# clock_rev0.net
KiCad netlist of a schematic drawn in EAGLE
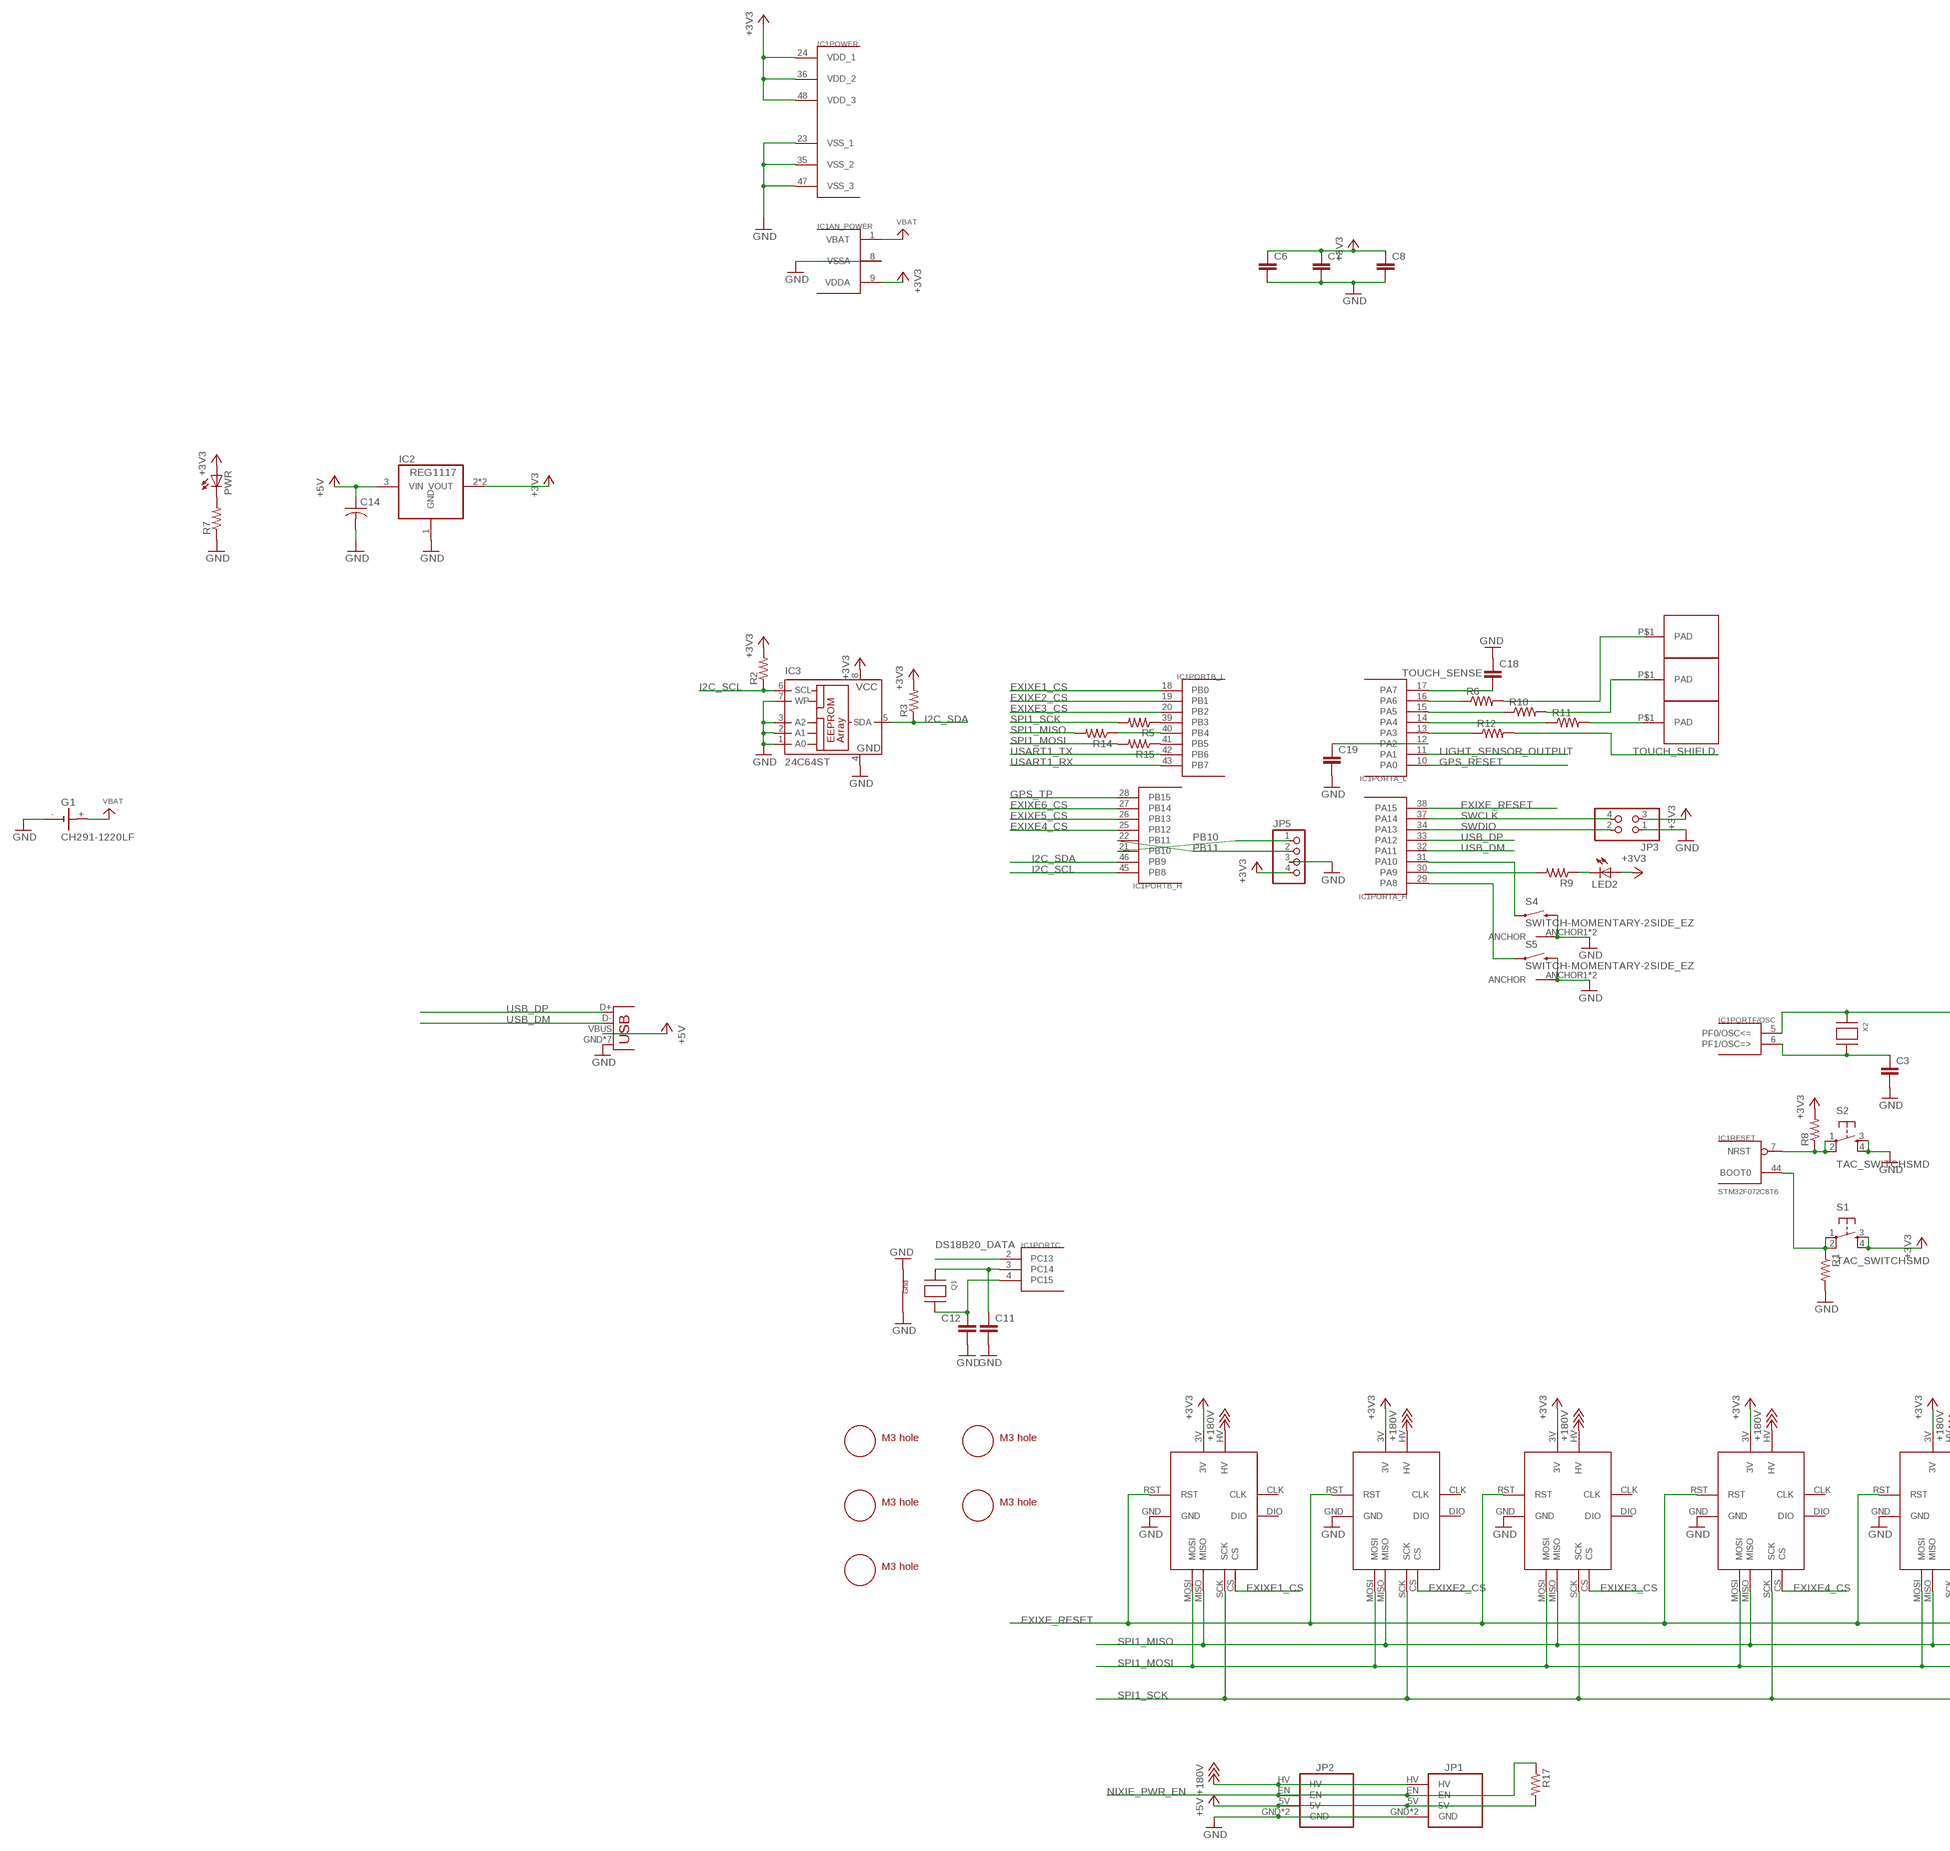
[diagram p0: schematic, sheet 1, part 1 of 2]
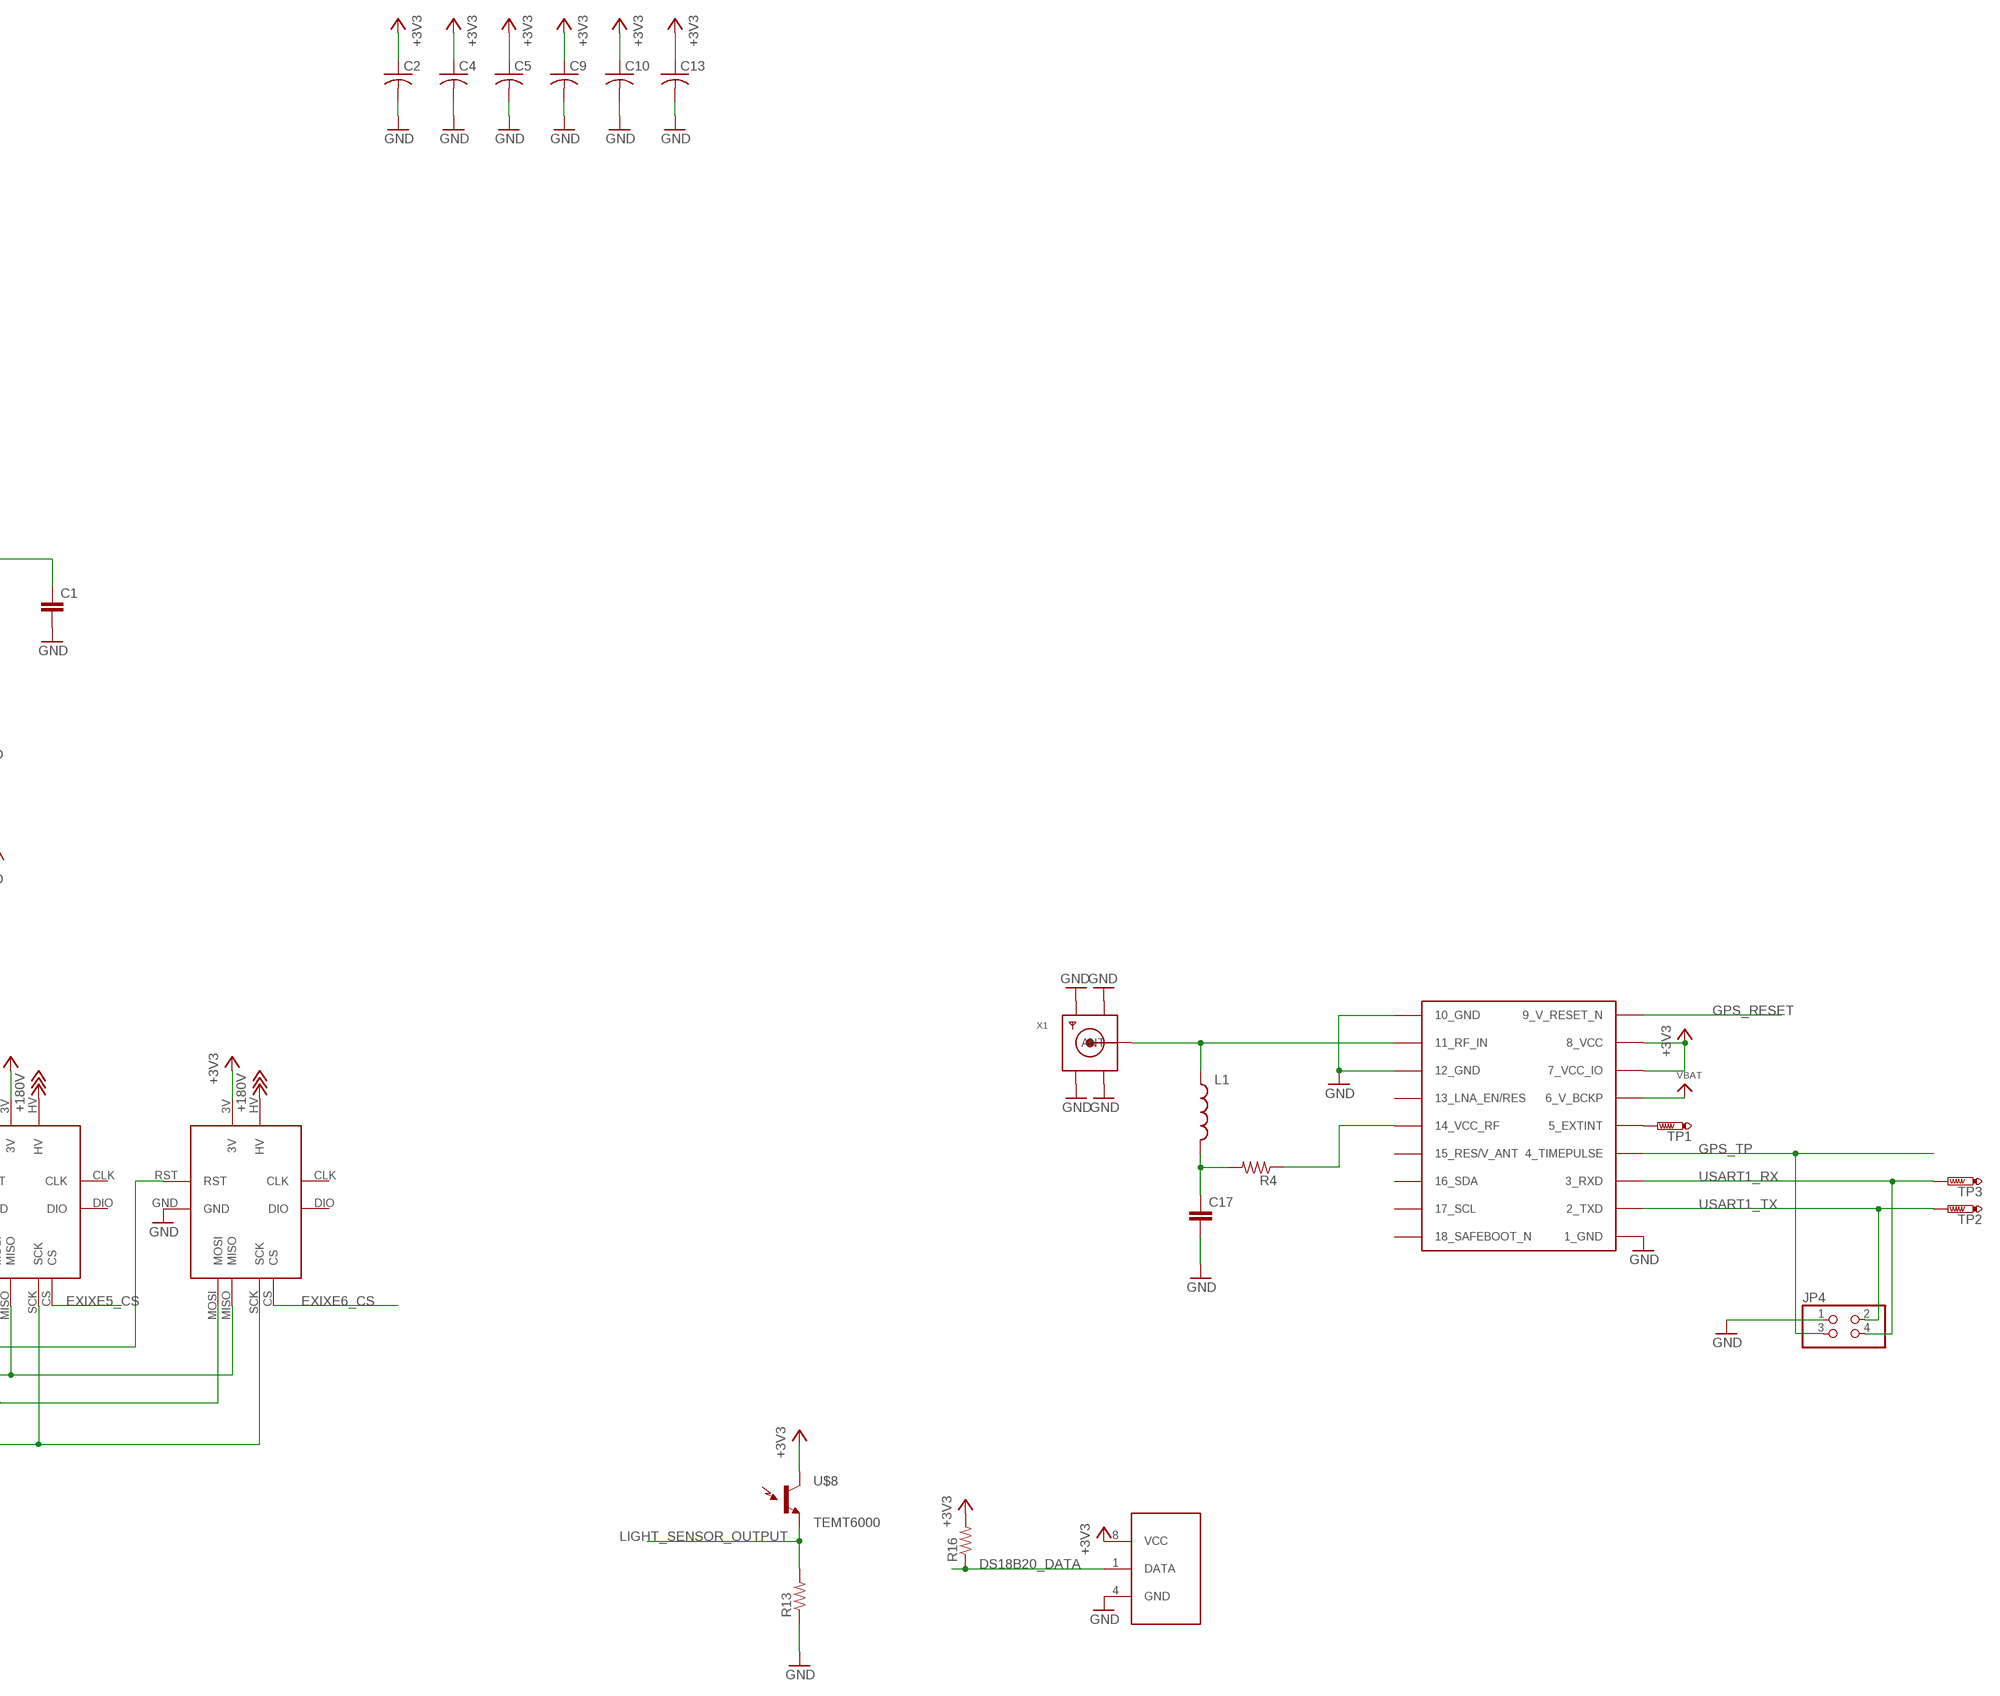
[diagram p1: schematic, sheet 1, part 2 of 2]

(export (version "E")
  (design (tool "Eeschema 10.0.6"))
  (components
    (comp (ref "C1")
      (value "CAP0805")
      (footprint "eagle-import:0805")
      (libsource (lib "eagle-import") (part "CAP0805"))
    )
    (comp (ref "C2")
      (value "C-USC1210")
      (footprint "eagle-import:C1210")
      (libsource (lib "eagle-import") (part "C-USC1210"))
    )
    (comp (ref "C3")
      (value "CAP0805")
      (footprint "eagle-import:0805")
      (libsource (lib "eagle-import") (part "CAP0805"))
    )
    (comp (ref "C4")
      (value "C-USC1210")
      (footprint "eagle-import:C1210")
      (libsource (lib "eagle-import") (part "C-USC1210"))
    )
    (comp (ref "C5")
      (value "C-USC1210")
      (footprint "eagle-import:C1210")
      (libsource (lib "eagle-import") (part "C-USC1210"))
    )
    (comp (ref "C6")
      (value "CAP0805")
      (footprint "eagle-import:0805")
      (libsource (lib "eagle-import") (part "CAP0805"))
    )
    (comp (ref "C7")
      (value "CAP0805")
      (footprint "eagle-import:0805")
      (libsource (lib "eagle-import") (part "CAP0805"))
    )
    (comp (ref "C8")
      (value "CAP0805")
      (footprint "eagle-import:0805")
      (libsource (lib "eagle-import") (part "CAP0805"))
    )
    (comp (ref "C9")
      (value "C-USC1210")
      (footprint "eagle-import:C1210")
      (libsource (lib "eagle-import") (part "C-USC1210"))
    )
    (comp (ref "C10")
      (value "C-USC1210")
      (footprint "eagle-import:C1210")
      (libsource (lib "eagle-import") (part "C-USC1210"))
    )
    (comp (ref "C11")
      (value "CAP0805")
      (footprint "eagle-import:0805")
      (libsource (lib "eagle-import") (part "CAP0805"))
    )
    (comp (ref "C12")
      (value "CAP0805")
      (footprint "eagle-import:0805")
      (libsource (lib "eagle-import") (part "CAP0805"))
    )
    (comp (ref "C13")
      (value "C-USC1210")
      (footprint "eagle-import:C1210")
      (libsource (lib "eagle-import") (part "C-USC1210"))
    )
    (comp (ref "C14")
      (value "C-USC1210")
      (footprint "eagle-import:C1210")
      (libsource (lib "eagle-import") (part "C-USC1210"))
    )
    (comp (ref "C17")
      (value "CAP0805")
      (footprint "eagle-import:0805")
      (libsource (lib "eagle-import") (part "CAP0805"))
    )
    (comp (ref "C18")
      (value "CAP0805")
      (footprint "eagle-import:0805")
      (libsource (lib "eagle-import") (part "CAP0805"))
    )
    (comp (ref "C19")
      (value "CAP0805")
      (footprint "eagle-import:0805")
      (libsource (lib "eagle-import") (part "CAP0805"))
    )
    (comp (ref "G1")
      (value "CH291-1220LF")
      (footprint "eagle-import:CH291-1220LF")
      (libsource (lib "eagle-import") (part "CH291-1220LF"))
    )
    (comp (ref "IC1")
      (value "STM32F072C8T6")
      (footprint "eagle-import:TQFP48")
      (libsource (lib "eagle-import") (part "STM32F072C8T6"))
    )
    (comp (ref "IC2")
      (value "REG1117")
      (footprint "eagle-import:SOT223")
      (libsource (lib "eagle-import") (part "REG1117"))
    )
    (comp (ref "IC3")
      (value "24C64ST")
      (footprint "eagle-import:TSSOP8")
      (fields (field (name "MPN") "CAT24C64YI-GT3"))
      (libsource (lib "eagle-import") (part "24STC64"))
    )
    (comp (ref "JP1")
      (value "EBAY_MODULEEBAY")
      (footprint "eagle-import:EBAY_PKG")
      (libsource (lib "eagle-import") (part "EBAY_MODULEEBAY"))
    )
    (comp (ref "JP2")
      (value "EBAY_MODULETAOBAO")
      (footprint "eagle-import:TAOBAO_PKG")
      (libsource (lib "eagle-import") (part "EBAY_MODULETAOBAO"))
    )
    (comp (ref "JP3")
      (value "PINHD-2X2")
      (footprint "eagle-import:2X02")
      (libsource (lib "eagle-import") (part "PINHD-2X2"))
    )
    (comp (ref "JP4")
      (value "PINHD-2X2")
      (footprint "eagle-import:2X02")
      (libsource (lib "eagle-import") (part "PINHD-2X2"))
    )
    (comp (ref "JP5")
      (value "PINHD-1X4")
      (footprint "eagle-import:1X04")
      (libsource (lib "eagle-import") (part "PINHD-1X4"))
    )
    (comp (ref "L1")
      (value "INDUCTOR0805")
      (footprint "eagle-import:0805")
      (libsource (lib "eagle-import") (part "INDUCTOR0805"))
    )
    (comp (ref "LED2")
      (value "LEDCHIP-LED0805")
      (footprint "eagle-import:CHIP-LED0805")
      (libsource (lib "eagle-import") (part "LEDCHIP-LED0805"))
    )
    (comp (ref "PWR")
      (value "LEDCHIP-LED0805")
      (footprint "eagle-import:CHIP-LED0805")
      (libsource (lib "eagle-import") (part "LEDCHIP-LED0805"))
    )
    (comp (ref "Q1")
      (value "XTAL-4-3225")
      (footprint "eagle-import:NX3225")
      (libsource (lib "eagle-import") (part "XTAL-4-3225"))
    )
    (comp (ref "R1")
      (value "RESISTOR0805-RES")
      (footprint "eagle-import:0805")
      (libsource (lib "eagle-import") (part "RESISTOR0805-RES"))
    )
    (comp (ref "R2")
      (value "RESISTOR0805-RES")
      (footprint "eagle-import:0805")
      (libsource (lib "eagle-import") (part "RESISTOR0805-RES"))
    )
    (comp (ref "R3")
      (value "RESISTOR0805-RES")
      (footprint "eagle-import:0805")
      (libsource (lib "eagle-import") (part "RESISTOR0805-RES"))
    )
    (comp (ref "R4")
      (value "RESISTOR0805-RES")
      (footprint "eagle-import:0805")
      (libsource (lib "eagle-import") (part "RESISTOR0805-RES"))
    )
    (comp (ref "R5")
      (value "RESISTOR0805-RES")
      (footprint "eagle-import:0805")
      (libsource (lib "eagle-import") (part "RESISTOR0805-RES"))
    )
    (comp (ref "R6")
      (value "RESISTOR0805-RES")
      (footprint "eagle-import:0805")
      (libsource (lib "eagle-import") (part "RESISTOR0805-RES"))
    )
    (comp (ref "R7")
      (value "RESISTOR0805-RES")
      (footprint "eagle-import:0805")
      (libsource (lib "eagle-import") (part "RESISTOR0805-RES"))
    )
    (comp (ref "R8")
      (value "RESISTOR0805-RES")
      (footprint "eagle-import:0805")
      (libsource (lib "eagle-import") (part "RESISTOR0805-RES"))
    )
    (comp (ref "R9")
      (value "RESISTOR0805-RES")
      (footprint "eagle-import:0805")
      (libsource (lib "eagle-import") (part "RESISTOR0805-RES"))
    )
    (comp (ref "R10")
      (value "RESISTOR0805-RES")
      (footprint "eagle-import:0805")
      (libsource (lib "eagle-import") (part "RESISTOR0805-RES"))
    )
    (comp (ref "R11")
      (value "RESISTOR0805-RES")
      (footprint "eagle-import:0805")
      (libsource (lib "eagle-import") (part "RESISTOR0805-RES"))
    )
    (comp (ref "R12")
      (value "RESISTOR0805-RES")
      (footprint "eagle-import:0805")
      (libsource (lib "eagle-import") (part "RESISTOR0805-RES"))
    )
    (comp (ref "R13")
      (value "RESISTOR0805-RES")
      (footprint "eagle-import:0805")
      (libsource (lib "eagle-import") (part "RESISTOR0805-RES"))
    )
    (comp (ref "R14")
      (value "RESISTOR0805-RES")
      (footprint "eagle-import:0805")
      (libsource (lib "eagle-import") (part "RESISTOR0805-RES"))
    )
    (comp (ref "R15")
      (value "RESISTOR0805-RES")
      (footprint "eagle-import:0805")
      (libsource (lib "eagle-import") (part "RESISTOR0805-RES"))
    )
    (comp (ref "R16")
      (value "RESISTOR0805-RES")
      (footprint "eagle-import:0805")
      (libsource (lib "eagle-import") (part "RESISTOR0805-RES"))
    )
    (comp (ref "R17")
      (value "RESISTOR0805-RES")
      (footprint "eagle-import:0805")
      (libsource (lib "eagle-import") (part "RESISTOR0805-RES"))
    )
    (comp (ref "S1")
      (value "TAC_SWITCHSMD")
      (footprint "eagle-import:TACTILE-SWITCH-SMD")
      (libsource (lib "eagle-import") (part "TAC_SWITCHSMD"))
    )
    (comp (ref "S2")
      (value "TAC_SWITCHSMD")
      (footprint "eagle-import:TACTILE-SWITCH-SMD")
      (libsource (lib "eagle-import") (part "TAC_SWITCHSMD"))
    )
    (comp (ref "S4")
      (value "SWITCH-MOMENTARY-2SIDE_EZ")
      (footprint "eagle-import:TACTILE-PTH-SIDEEZ")
      (libsource (lib "eagle-import") (part "SWITCH-MOMENTARY-2SIDE_EZ"))
    )
    (comp (ref "S5")
      (value "SWITCH-MOMENTARY-2SIDE_EZ")
      (footprint "eagle-import:TACTILE-PTH-SIDEEZ")
      (libsource (lib "eagle-import") (part "SWITCH-MOMENTARY-2SIDE_EZ"))
    )
    (comp (ref "TP1")
      (value "PTR1TP20R")
      (footprint "eagle-import:TP20R")
      (libsource (lib "eagle-import") (part "PTR1TP20R"))
    )
    (comp (ref "TP2")
      (value "PTR1TP20R")
      (footprint "eagle-import:TP20R")
      (libsource (lib "eagle-import") (part "PTR1TP20R"))
    )
    (comp (ref "TP3")
      (value "PTR1TP20R")
      (footprint "eagle-import:TP20R")
      (libsource (lib "eagle-import") (part "PTR1TP20R"))
    )
    (comp (ref "U$1")
      (value "EXIXE")
      (footprint "eagle-import:EXIXE_PAC")
      (libsource (lib "eagle-import") (part "EXIXE"))
    )
    (comp (ref "U$2")
      (value "EXIXE")
      (footprint "eagle-import:EXIXE_PAC")
      (libsource (lib "eagle-import") (part "EXIXE"))
    )
    (comp (ref "U$3")
      (value "EXIXE")
      (footprint "eagle-import:EXIXE_PAC")
      (libsource (lib "eagle-import") (part "EXIXE"))
    )
    (comp (ref "U$4")
      (value "EXIXE")
      (footprint "eagle-import:EXIXE_PAC")
      (libsource (lib "eagle-import") (part "EXIXE"))
    )
    (comp (ref "U$5")
      (value "EXIXE")
      (footprint "eagle-import:EXIXE_PAC")
      (libsource (lib "eagle-import") (part "EXIXE"))
    )
    (comp (ref "U$6")
      (value "EXIXE")
      (footprint "eagle-import:EXIXE_PAC")
      (libsource (lib "eagle-import") (part "EXIXE"))
    )
    (comp (ref "U$7")
      (value "MAX-M8")
      (footprint "eagle-import:MAX-M8")
      (libsource (lib "eagle-import") (part "MAX-M8"))
    )
    (comp (ref "U$8")
      (value "TEMT6000")
      (footprint "eagle-import:TEMT6000-SEN")
      (libsource (lib "eagle-import") (part "TEMT6000"))
    )
    (comp (ref "U$9")
      (value "DS18B20")
      (footprint "eagle-import:MSOP8")
      (libsource (lib "eagle-import") (part "DS18B20"))
    )
    (comp (ref "U$10")
      (value "M3_MOUNTING_HOLE")
      (footprint "eagle-import:M3_MOUNTING_HOLE_PACK")
      (libsource (lib "eagle-import") (part "M3_MOUNTING_HOLE"))
    )
    (comp (ref "U$11")
      (value "M3_MOUNTING_HOLE")
      (footprint "eagle-import:M3_MOUNTING_HOLE_PACK")
      (libsource (lib "eagle-import") (part "M3_MOUNTING_HOLE"))
    )
    (comp (ref "U$12")
      (value "M3_MOUNTING_HOLE")
      (footprint "eagle-import:M3_MOUNTING_HOLE_PACK")
      (libsource (lib "eagle-import") (part "M3_MOUNTING_HOLE"))
    )
    (comp (ref "U$13")
      (value "M3_MOUNTING_HOLE")
      (footprint "eagle-import:M3_MOUNTING_HOLE_PACK")
      (libsource (lib "eagle-import") (part "M3_MOUNTING_HOLE"))
    )
    (comp (ref "U$14")
      (value "TOUCHPAD")
      (footprint "eagle-import:TOUCHPAD_PAK")
      (libsource (lib "eagle-import") (part "TOUCHPAD"))
    )
    (comp (ref "U$15")
      (value "TOUCHPAD")
      (footprint "eagle-import:TOUCHPAD_PAK")
      (libsource (lib "eagle-import") (part "TOUCHPAD"))
    )
    (comp (ref "U$16")
      (value "TOUCHPAD")
      (footprint "eagle-import:TOUCHPAD_PAK")
      (libsource (lib "eagle-import") (part "TOUCHPAD"))
    )
    (comp (ref "U$20")
      (value "M3_MOUNTING_HOLE")
      (footprint "eagle-import:M3_MOUNTING_HOLE_PACK")
      (libsource (lib "eagle-import") (part "M3_MOUNTING_HOLE"))
    )
    (comp (ref "X1")
      (value "SMACONNECTOR")
      (footprint "eagle-import:SMA90_DIP")
      (libsource (lib "eagle-import") (part "SMACONNECTOR"))
    )
    (comp (ref "X2")
      (value "XTAL-3.2X1.5")
      (footprint "eagle-import:XTAL3215")
      (libsource (lib "eagle-import") (part "XTAL-3.2X1.5"))
    )
    (comp (ref "X3")
      (value "USB-MICROB")
      (footprint "eagle-import:USB-MICROB")
      (libsource (lib "eagle-import") (part "USB-MICROB"))
    )
  )
  (nets
    (net (code "1") (name "+3V3") (class "Default")
      (node (ref "C10") (pin "1") (pinfunction "1_1") (pintype "passive"))
      (node (ref "C13") (pin "1") (pinfunction "1_1") (pintype "passive"))
      (node (ref "C2") (pin "1") (pinfunction "1_1") (pintype "passive"))
      (node (ref "C4") (pin "1") (pinfunction "1_1") (pintype "passive"))
      (node (ref "C5") (pin "1") (pinfunction "1_1") (pintype "passive"))
      (node (ref "C6") (pin "1") (pinfunction "1_1") (pintype "passive"))
      (node (ref "C7") (pin "1") (pinfunction "1_1") (pintype "passive"))
      (node (ref "C8") (pin "1") (pinfunction "1_1") (pintype "passive"))
      (node (ref "C9") (pin "1") (pinfunction "1_1") (pintype "passive"))
      (node (ref "IC1") (pin "24") (pinfunction "VDD_1_24") (pintype "power_in"))
      (node (ref "IC1") (pin "36") (pinfunction "VDD_2_36") (pintype "power_in"))
      (node (ref "IC1") (pin "48") (pinfunction "VDD_3_48") (pintype "power_in"))
      (node (ref "IC1") (pin "9") (pinfunction "VDDA_9") (pintype "power_in"))
      (node (ref "IC2") (pin "2") (pinfunction "VOUT_2") (pintype "output"))
      (node (ref "IC2") (pin "4") (pinfunction "VOUT_4") (pintype "output"))
      (node (ref "IC3") (pin "8") (pinfunction "VCC_8") (pintype "power_in"))
      (node (ref "JP3") (pin "3") (pinfunction "3_3") (pintype "passive"))
      (node (ref "JP5") (pin "4") (pinfunction "4_4") (pintype "passive"))
      (node (ref "LED2") (pin "A") (pinfunction "A_A") (pintype "passive"))
      (node (ref "PWR") (pin "A") (pinfunction "A_A") (pintype "passive"))
      (node (ref "R16") (pin "2") (pinfunction "2_2") (pintype "passive"))
      (node (ref "R2") (pin "2") (pinfunction "2_2") (pintype "passive"))
      (node (ref "R3") (pin "2") (pinfunction "2_2") (pintype "passive"))
      (node (ref "R8") (pin "2") (pinfunction "2_2") (pintype "passive"))
      (node (ref "S1") (pin "3") (pinfunction "3_3") (pintype "passive"))
      (node (ref "S1") (pin "4") (pinfunction "4_4") (pintype "passive"))
      (node (ref "U$1") (pin "3V") (pinfunction "3V_3V") (pintype "bidirectional"))
      (node (ref "U$2") (pin "3V") (pinfunction "3V_3V") (pintype "bidirectional"))
      (node (ref "U$3") (pin "3V") (pinfunction "3V_3V") (pintype "bidirectional"))
      (node (ref "U$4") (pin "3V") (pinfunction "3V_3V") (pintype "bidirectional"))
      (node (ref "U$5") (pin "3V") (pinfunction "3V_3V") (pintype "bidirectional"))
      (node (ref "U$6") (pin "3V") (pinfunction "3V_3V") (pintype "bidirectional"))
      (node (ref "U$7") (pin "7_VCC_IO") (pinfunction "7_VCC_IO_7_VCC_IO") (pintype "power_in"))
      (node (ref "U$7") (pin "8_VCC") (pinfunction "8_VCC_8_VCC") (pintype "power_in"))
      (node (ref "U$8") (pin "COLLECTOR") (pinfunction "C1_COLLECTOR") (pintype "passive"))
      (node (ref "U$9") (pin "8") (pinfunction "VCC_8") (pintype "bidirectional"))
    )
    (net (code "2") (name "+5V") (class "Default")
      (node (ref "C14") (pin "1") (pinfunction "1_1") (pintype "passive"))
      (node (ref "IC2") (pin "3") (pinfunction "VIN_3") (pintype "input"))
      (node (ref "JP1") (pin "5V") (pinfunction "5V_5V") (pintype "bidirectional"))
      (node (ref "JP2") (pin "5V") (pinfunction "5V_5V") (pintype "bidirectional"))
      (node (ref "R17") (pin "2") (pinfunction "2_2") (pintype "passive"))
      (node (ref "X3") (pin "VBUS") (pinfunction "VBUS_VBUS") (pintype "bidirectional"))
    )
    (net (code "3") (name "+180V") (class "Default")
      (node (ref "JP1") (pin "HV") (pinfunction "HV_HV") (pintype "bidirectional"))
      (node (ref "JP2") (pin "HV") (pinfunction "HV_HV") (pintype "bidirectional"))
      (node (ref "U$1") (pin "HV") (pinfunction "HV_HV") (pintype "bidirectional"))
      (node (ref "U$2") (pin "HV") (pinfunction "HV_HV") (pintype "bidirectional"))
      (node (ref "U$3") (pin "HV") (pinfunction "HV_HV") (pintype "bidirectional"))
      (node (ref "U$4") (pin "HV") (pinfunction "HV_HV") (pintype "bidirectional"))
      (node (ref "U$5") (pin "HV") (pinfunction "HV_HV") (pintype "bidirectional"))
      (node (ref "U$6") (pin "HV") (pinfunction "HV_HV") (pintype "bidirectional"))
    )
    (net (code "4") (name "/DS18B20_DATA") (class "Default")
      (node (ref "IC1") (pin "2") (pinfunction "PC13_2") (pintype "bidirectional"))
      (node (ref "R16") (pin "1") (pinfunction "1_1") (pintype "passive"))
      (node (ref "U$9") (pin "1") (pinfunction "DATA_1") (pintype "bidirectional"))
    )
    (net (code "5") (name "/EXIXE1_CS") (class "Default")
      (node (ref "IC1") (pin "18") (pinfunction "PB0_18") (pintype "bidirectional"))
      (node (ref "U$1") (pin "CS") (pinfunction "CS_CS") (pintype "bidirectional"))
    )
    (net (code "6") (name "/EXIXE2_CS") (class "Default")
      (node (ref "IC1") (pin "19") (pinfunction "PB1_19") (pintype "bidirectional"))
      (node (ref "U$2") (pin "CS") (pinfunction "CS_CS") (pintype "bidirectional"))
    )
    (net (code "7") (name "/EXIXE3_CS") (class "Default")
      (node (ref "IC1") (pin "20") (pinfunction "PB2_20") (pintype "bidirectional"))
      (node (ref "U$3") (pin "CS") (pinfunction "CS_CS") (pintype "bidirectional"))
    )
    (net (code "8") (name "/EXIXE4_CS") (class "Default")
      (node (ref "IC1") (pin "25") (pinfunction "PB12_25") (pintype "bidirectional"))
      (node (ref "U$4") (pin "CS") (pinfunction "CS_CS") (pintype "bidirectional"))
    )
    (net (code "9") (name "/EXIXE5_CS") (class "Default")
      (node (ref "IC1") (pin "26") (pinfunction "PB13_26") (pintype "bidirectional"))
      (node (ref "U$5") (pin "CS") (pinfunction "CS_CS") (pintype "bidirectional"))
    )
    (net (code "10") (name "/EXIXE6_CS") (class "Default")
      (node (ref "IC1") (pin "27") (pinfunction "PB14_27") (pintype "bidirectional"))
      (node (ref "U$6") (pin "CS") (pinfunction "CS_CS") (pintype "bidirectional"))
    )
    (net (code "11") (name "/EXIXE_RESET") (class "Default")
      (node (ref "IC1") (pin "38") (pinfunction "PA15_38") (pintype "bidirectional"))
      (node (ref "U$1") (pin "RST") (pinfunction "RST_RST") (pintype "bidirectional"))
      (node (ref "U$2") (pin "RST") (pinfunction "RST_RST") (pintype "bidirectional"))
      (node (ref "U$3") (pin "RST") (pinfunction "RST_RST") (pintype "bidirectional"))
      (node (ref "U$4") (pin "RST") (pinfunction "RST_RST") (pintype "bidirectional"))
      (node (ref "U$5") (pin "RST") (pinfunction "RST_RST") (pintype "bidirectional"))
      (node (ref "U$6") (pin "RST") (pinfunction "RST_RST") (pintype "bidirectional"))
    )
    (net (code "12") (name "/GPS_RESET") (class "Default")
      (node (ref "IC1") (pin "10") (pinfunction "PA0_10") (pintype "bidirectional"))
      (node (ref "U$7") (pin "9_RESET_N") (pinfunction "9_V_RESET_N_9_RESET_N") (pintype "power_in"))
    )
    (net (code "13") (name "/GPS_TP") (class "Default")
      (node (ref "IC1") (pin "28") (pinfunction "PB15_28") (pintype "bidirectional"))
      (node (ref "JP4") (pin "3") (pinfunction "3_3") (pintype "passive"))
      (node (ref "U$7") (pin "4_TIMEPULSE") (pinfunction "4_TIMEPULSE_4_TIMEPULSE") (pintype "bidirectional"))
    )
    (net (code "14") (name "/I2C_SCL") (class "Default")
      (node (ref "IC1") (pin "45") (pinfunction "PB8_45") (pintype "bidirectional"))
      (node (ref "IC3") (pin "6") (pinfunction "SCL_6") (pintype "input"))
      (node (ref "R2") (pin "1") (pinfunction "1_1") (pintype "passive"))
    )
    (net (code "15") (name "/I2C_SDA") (class "Default")
      (node (ref "IC1") (pin "46") (pinfunction "PB9_46") (pintype "bidirectional"))
      (node (ref "IC3") (pin "5") (pinfunction "SDA_5") (pintype "bidirectional"))
      (node (ref "R3") (pin "1") (pinfunction "1_1") (pintype "passive"))
    )
    (net (code "16") (name "/LIGHT_SENSOR_OUTPUT") (class "Default")
      (node (ref "IC1") (pin "11") (pinfunction "PA1_11") (pintype "bidirectional"))
      (node (ref "R13") (pin "2") (pinfunction "2_2") (pintype "passive"))
      (node (ref "U$8") (pin "EMITTER") (pinfunction "E1_EMITTER") (pintype "passive"))
    )
    (net (code "17") (name "/NIXIE_PWR_EN") (class "Default")
      (node (ref "JP1") (pin "EN") (pinfunction "EN_EN") (pintype "bidirectional"))
      (node (ref "JP2") (pin "EN") (pinfunction "EN_EN") (pintype "bidirectional"))
      (node (ref "R17") (pin "1") (pinfunction "1_1") (pintype "passive"))
    )
    (net (code "18") (name "/PB10") (class "Default")
      (node (ref "IC1") (pin "21") (pinfunction "PB10_21") (pintype "bidirectional"))
      (node (ref "JP5") (pin "1") (pinfunction "1_1") (pintype "passive"))
    )
    (net (code "19") (name "/PB11") (class "Default")
      (node (ref "IC1") (pin "22") (pinfunction "PB11_22") (pintype "bidirectional"))
      (node (ref "JP5") (pin "2") (pinfunction "2_2") (pintype "passive"))
    )
    (net (code "20") (name "/SPI1_MISO") (class "Default")
      (node (ref "R14") (pin "2") (pinfunction "2_2") (pintype "passive"))
      (node (ref "U$1") (pin "MISO") (pinfunction "MISO_MISO") (pintype "bidirectional"))
      (node (ref "U$2") (pin "MISO") (pinfunction "MISO_MISO") (pintype "bidirectional"))
      (node (ref "U$3") (pin "MISO") (pinfunction "MISO_MISO") (pintype "bidirectional"))
      (node (ref "U$4") (pin "MISO") (pinfunction "MISO_MISO") (pintype "bidirectional"))
      (node (ref "U$5") (pin "MISO") (pinfunction "MISO_MISO") (pintype "bidirectional"))
      (node (ref "U$6") (pin "MISO") (pinfunction "MISO_MISO") (pintype "bidirectional"))
    )
    (net (code "21") (name "/SPI1_MOSI") (class "Default")
      (node (ref "R15") (pin "2") (pinfunction "2_2") (pintype "passive"))
      (node (ref "U$1") (pin "MOSI") (pinfunction "MOSI_MOSI") (pintype "bidirectional"))
      (node (ref "U$2") (pin "MOSI") (pinfunction "MOSI_MOSI") (pintype "bidirectional"))
      (node (ref "U$3") (pin "MOSI") (pinfunction "MOSI_MOSI") (pintype "bidirectional"))
      (node (ref "U$4") (pin "MOSI") (pinfunction "MOSI_MOSI") (pintype "bidirectional"))
      (node (ref "U$5") (pin "MOSI") (pinfunction "MOSI_MOSI") (pintype "bidirectional"))
      (node (ref "U$6") (pin "MOSI") (pinfunction "MOSI_MOSI") (pintype "bidirectional"))
    )
    (net (code "22") (name "/SPI1_SCK") (class "Default")
      (node (ref "R5") (pin "2") (pinfunction "2_2") (pintype "passive"))
      (node (ref "U$1") (pin "SCK") (pinfunction "SCK_SCK") (pintype "bidirectional"))
      (node (ref "U$2") (pin "SCK") (pinfunction "SCK_SCK") (pintype "bidirectional"))
      (node (ref "U$3") (pin "SCK") (pinfunction "SCK_SCK") (pintype "bidirectional"))
      (node (ref "U$4") (pin "SCK") (pinfunction "SCK_SCK") (pintype "bidirectional"))
      (node (ref "U$5") (pin "SCK") (pinfunction "SCK_SCK") (pintype "bidirectional"))
      (node (ref "U$6") (pin "SCK") (pinfunction "SCK_SCK") (pintype "bidirectional"))
    )
    (net (code "23") (name "/SWCLK") (class "Default")
      (node (ref "IC1") (pin "37") (pinfunction "PA14_37") (pintype "bidirectional"))
      (node (ref "JP3") (pin "4") (pinfunction "4_4") (pintype "passive"))
    )
    (net (code "24") (name "/SWDIO") (class "Default")
      (node (ref "IC1") (pin "34") (pinfunction "PA13_34") (pintype "bidirectional"))
      (node (ref "JP3") (pin "2") (pinfunction "2_2") (pintype "passive"))
    )
    (net (code "25") (name "/TOUCH_SENSE") (class "Default")
      (node (ref "C18") (pin "2") (pinfunction "2_2") (pintype "passive"))
      (node (ref "IC1") (pin "17") (pinfunction "PA7_17") (pintype "bidirectional"))
    )
    (net (code "26") (name "/TOUCH_SHIELD") (class "Default")
      (node (ref "R12") (pin "2") (pinfunction "2_2") (pintype "passive"))
    )
    (net (code "27") (name "/USART1_RX") (class "Default")
      (node (ref "IC1") (pin "43") (pinfunction "PB7_43") (pintype "bidirectional"))
      (node (ref "JP4") (pin "4") (pinfunction "4_4") (pintype "passive"))
      (node (ref "TP3") (pin "TP") (pinfunction "TP_TP") (pintype "input"))
      (node (ref "U$7") (pin "3_RXD") (pinfunction "3_RXD_3_RXD") (pintype "bidirectional"))
    )
    (net (code "28") (name "/USART1_TX") (class "Default")
      (node (ref "IC1") (pin "42") (pinfunction "PB6_42") (pintype "bidirectional"))
      (node (ref "JP4") (pin "2") (pinfunction "2_2") (pintype "passive"))
      (node (ref "TP2") (pin "TP") (pinfunction "TP_TP") (pintype "input"))
      (node (ref "U$7") (pin "2_TXD") (pinfunction "2_TXD_2_TXD") (pintype "bidirectional"))
    )
    (net (code "29") (name "/USB_DM") (class "Default")
      (node (ref "IC1") (pin "32") (pinfunction "PA11_32") (pintype "bidirectional"))
      (node (ref "X3") (pin "D-") (pinfunction "D-_D-") (pintype "bidirectional"))
    )
    (net (code "30") (name "/USB_DP") (class "Default")
      (node (ref "IC1") (pin "33") (pinfunction "PA12_33") (pintype "bidirectional"))
      (node (ref "X3") (pin "D+") (pinfunction "D+_D+") (pintype "bidirectional"))
    )
    (net (code "31") (name "GND") (class "Default")
      (node (ref "C1") (pin "2") (pinfunction "2_2") (pintype "passive"))
      (node (ref "C10") (pin "2") (pinfunction "2_2") (pintype "passive"))
      (node (ref "C11") (pin "2") (pinfunction "2_2") (pintype "passive"))
      (node (ref "C12") (pin "2") (pinfunction "2_2") (pintype "passive"))
      (node (ref "C13") (pin "2") (pinfunction "2_2") (pintype "passive"))
      (node (ref "C14") (pin "2") (pinfunction "2_2") (pintype "passive"))
      (node (ref "C17") (pin "2") (pinfunction "2_2") (pintype "passive"))
      (node (ref "C18") (pin "1") (pinfunction "1_1") (pintype "passive"))
      (node (ref "C19") (pin "2") (pinfunction "2_2") (pintype "passive"))
      (node (ref "C2") (pin "2") (pinfunction "2_2") (pintype "passive"))
      (node (ref "C3") (pin "2") (pinfunction "2_2") (pintype "passive"))
      (node (ref "C4") (pin "2") (pinfunction "2_2") (pintype "passive"))
      (node (ref "C5") (pin "2") (pinfunction "2_2") (pintype "passive"))
      (node (ref "C6") (pin "2") (pinfunction "2_2") (pintype "passive"))
      (node (ref "C7") (pin "2") (pinfunction "2_2") (pintype "passive"))
      (node (ref "C8") (pin "2") (pinfunction "2_2") (pintype "passive"))
      (node (ref "C9") (pin "2") (pinfunction "2_2") (pintype "passive"))
      (node (ref "G1") (pin "-") (pinfunction "-_-") (pintype "passive"))
      (node (ref "IC1") (pin "23") (pinfunction "VSS_1_23") (pintype "power_in"))
      (node (ref "IC1") (pin "35") (pinfunction "VSS_2_35") (pintype "power_in"))
      (node (ref "IC1") (pin "47") (pinfunction "VSS_3_47") (pintype "power_in"))
      (node (ref "IC1") (pin "8") (pinfunction "VSSA_8") (pintype "power_in"))
      (node (ref "IC2") (pin "1") (pinfunction "GND_1") (pintype "power_in"))
      (node (ref "IC3") (pin "1") (pinfunction "A0_1") (pintype "input"))
      (node (ref "IC3") (pin "2") (pinfunction "A1_2") (pintype "input"))
      (node (ref "IC3") (pin "3") (pinfunction "A2_3") (pintype "input"))
      (node (ref "IC3") (pin "4") (pinfunction "GND_4") (pintype "power_in"))
      (node (ref "IC3") (pin "7") (pinfunction "WP_7") (pintype "input"))
      (node (ref "JP1") (pin "GND") (pinfunction "GND_GND") (pintype "bidirectional"))
      (node (ref "JP1") (pin "GND2") (pinfunction "GND_GND2") (pintype "bidirectional"))
      (node (ref "JP2") (pin "GND") (pinfunction "GND_GND") (pintype "bidirectional"))
      (node (ref "JP2") (pin "GND2") (pinfunction "GND_GND2") (pintype "bidirectional"))
      (node (ref "JP3") (pin "1") (pinfunction "1_1") (pintype "passive"))
      (node (ref "JP4") (pin "1") (pinfunction "1_1") (pintype "passive"))
      (node (ref "JP5") (pin "3") (pinfunction "3_3") (pintype "passive"))
      (node (ref "Q1") (pin "2") (pinfunction "G2_2") (pintype "power_in"))
      (node (ref "Q1") (pin "4") (pinfunction "G1_4") (pintype "power_in"))
      (node (ref "R1") (pin "2") (pinfunction "2_2") (pintype "passive"))
      (node (ref "R13") (pin "1") (pinfunction "1_1") (pintype "passive"))
      (node (ref "R7") (pin "1") (pinfunction "1_1") (pintype "passive"))
      (node (ref "S2") (pin "3") (pinfunction "3_3") (pintype "passive"))
      (node (ref "S2") (pin "4") (pinfunction "4_4") (pintype "passive"))
      (node (ref "S4") (pin "2") (pinfunction "2_2") (pintype "passive"))
      (node (ref "S4") (pin "ANCHOR1") (pinfunction "ANCHOR_ANCHOR1") (pintype "bidirectional"))
      (node (ref "S4") (pin "ANCHOR2") (pinfunction "ANCHOR_ANCHOR2") (pintype "bidirectional"))
      (node (ref "S5") (pin "2") (pinfunction "2_2") (pintype "passive"))
      (node (ref "S5") (pin "ANCHOR1") (pinfunction "ANCHOR_ANCHOR1") (pintype "bidirectional"))
      (node (ref "S5") (pin "ANCHOR2") (pinfunction "ANCHOR_ANCHOR2") (pintype "bidirectional"))
      (node (ref "U$1") (pin "GND") (pinfunction "GND_GND") (pintype "bidirectional"))
      (node (ref "U$2") (pin "GND") (pinfunction "GND_GND") (pintype "bidirectional"))
      (node (ref "U$3") (pin "GND") (pinfunction "GND_GND") (pintype "bidirectional"))
      (node (ref "U$4") (pin "GND") (pinfunction "GND_GND") (pintype "bidirectional"))
      (node (ref "U$5") (pin "GND") (pinfunction "GND_GND") (pintype "bidirectional"))
      (node (ref "U$6") (pin "GND") (pinfunction "GND_GND") (pintype "bidirectional"))
      (node (ref "U$7") (pin "10_GND") (pinfunction "10_GND_10_GND") (pintype "power_in"))
      (node (ref "U$7") (pin "12_GND") (pinfunction "12_GND_12_GND") (pintype "power_in"))
      (node (ref "U$7") (pin "1_GND") (pinfunction "1_GND_1_GND") (pintype "power_in"))
      (node (ref "U$9") (pin "4") (pinfunction "GND_4") (pintype "bidirectional"))
      (node (ref "X1") (pin "GND1") (pinfunction "GND1_GND1") (pintype "power_in"))
      (node (ref "X1") (pin "GND2") (pinfunction "GND2_GND2") (pintype "power_in"))
      (node (ref "X1") (pin "GND3") (pinfunction "GND3_GND3") (pintype "power_in"))
      (node (ref "X1") (pin "GND4") (pinfunction "GND4_GND4") (pintype "power_in"))
      (node (ref "X3") (pin "GND") (pinfunction "GND_GND") (pintype "bidirectional"))
      (node (ref "X3") (pin "P1") (pinfunction "GND_P1") (pintype "bidirectional"))
      (node (ref "X3") (pin "P2") (pinfunction "GND_P2") (pintype "bidirectional"))
      (node (ref "X3") (pin "P3") (pinfunction "GND_P3") (pintype "bidirectional"))
      (node (ref "X3") (pin "P4") (pinfunction "GND_P4") (pintype "bidirectional"))
      (node (ref "X3") (pin "P5") (pinfunction "GND_P5") (pintype "bidirectional"))
      (node (ref "X3") (pin "P6") (pinfunction "GND_P6") (pintype "bidirectional"))
    )
    (net (code "32") (name "Net-(C17-Pad1)") (class "Default")
      (node (ref "C17") (pin "1") (pinfunction "1_1") (pintype "passive"))
      (node (ref "L1") (pin "2") (pinfunction "2_2") (pintype "passive"))
      (node (ref "R4") (pin "2") (pinfunction "2_2") (pintype "passive"))
    )
    (net (code "33") (name "Net-(IC1B-PA8)") (class "Default")
      (node (ref "IC1") (pin "29") (pinfunction "PA8_29") (pintype "bidirectional"))
      (node (ref "S5") (pin "1") (pinfunction "1_1") (pintype "passive"))
    )
    (net (code "34") (name "Net-(IC1B-PA9)") (class "Default")
      (node (ref "IC1") (pin "30") (pinfunction "PA9_30") (pintype "bidirectional"))
      (node (ref "R9") (pin "2") (pinfunction "2_2") (pintype "passive"))
    )
    (net (code "35") (name "Net-(IC1B-PA10)") (class "Default")
      (node (ref "IC1") (pin "31") (pinfunction "PA10_31") (pintype "bidirectional"))
      (node (ref "S4") (pin "1") (pinfunction "1_1") (pintype "passive"))
    )
    (net (code "36") (name "Net-(IC1C-PA2)") (class "Default")
      (node (ref "C19") (pin "1") (pinfunction "1_1") (pintype "passive"))
      (node (ref "IC1") (pin "12") (pinfunction "PA2_12") (pintype "bidirectional"))
    )
    (net (code "37") (name "Net-(IC1C-PA3)") (class "Default")
      (node (ref "IC1") (pin "13") (pinfunction "PA3_13") (pintype "bidirectional"))
      (node (ref "R12") (pin "1") (pinfunction "1_1") (pintype "passive"))
    )
    (net (code "38") (name "Net-(IC1C-PA4)") (class "Default")
      (node (ref "IC1") (pin "14") (pinfunction "PA4_14") (pintype "bidirectional"))
      (node (ref "R11") (pin "1") (pinfunction "1_1") (pintype "passive"))
    )
    (net (code "39") (name "Net-(IC1C-PA5)") (class "Default")
      (node (ref "IC1") (pin "15") (pinfunction "PA5_15") (pintype "bidirectional"))
      (node (ref "R10") (pin "1") (pinfunction "1_1") (pintype "passive"))
    )
    (net (code "40") (name "Net-(IC1C-PA6)") (class "Default")
      (node (ref "IC1") (pin "16") (pinfunction "PA6_16") (pintype "bidirectional"))
      (node (ref "R6") (pin "1") (pinfunction "1_1") (pintype "passive"))
    )
    (net (code "41") (name "Net-(IC1E-PB3)") (class "Default")
      (node (ref "IC1") (pin "39") (pinfunction "PB3_39") (pintype "bidirectional"))
      (node (ref "R5") (pin "1") (pinfunction "1_1") (pintype "passive"))
    )
    (net (code "42") (name "Net-(IC1E-PB4)") (class "Default")
      (node (ref "IC1") (pin "40") (pinfunction "PB4_40") (pintype "bidirectional"))
      (node (ref "R14") (pin "1") (pinfunction "1_1") (pintype "passive"))
    )
    (net (code "43") (name "Net-(IC1E-PB5)") (class "Default")
      (node (ref "IC1") (pin "41") (pinfunction "PB5_41") (pintype "bidirectional"))
      (node (ref "R15") (pin "1") (pinfunction "1_1") (pintype "passive"))
    )
    (net (code "44") (name "Net-(IC1F-PC14)") (class "Default")
      (node (ref "C11") (pin "1") (pinfunction "1_1") (pintype "passive"))
      (node (ref "IC1") (pin "3") (pinfunction "PC14_3") (pintype "bidirectional"))
      (node (ref "Q1") (pin "1") (pinfunction "X1_1") (pintype "bidirectional"))
    )
    (net (code "45") (name "Net-(IC1F-PC15)") (class "Default")
      (node (ref "C12") (pin "1") (pinfunction "1_1") (pintype "passive"))
      (node (ref "IC1") (pin "4") (pinfunction "PC15_4") (pintype "bidirectional"))
      (node (ref "Q1") (pin "3") (pinfunction "X2_3") (pintype "bidirectional"))
    )
    (net (code "46") (name "Net-(IC1G-PF0{slash}OSC<=)") (class "Default")
      (node (ref "C1") (pin "1") (pinfunction "1_1") (pintype "passive"))
      (node (ref "IC1") (pin "5") (pinfunction "PF0/OSC<=_5") (pintype "bidirectional"))
      (node (ref "X2") (pin "P$1") (pinfunction "P$1_P$1") (pintype "bidirectional"))
    )
    (net (code "47") (name "Net-(IC1G-PF1{slash}OSC=>)") (class "Default")
      (node (ref "C3") (pin "1") (pinfunction "1_1") (pintype "passive"))
      (node (ref "IC1") (pin "6") (pinfunction "PF1/OSC=>_6") (pintype "bidirectional"))
      (node (ref "X2") (pin "P$2") (pinfunction "P$2_P$2") (pintype "bidirectional"))
    )
    (net (code "48") (name "Net-(IC1I-BOOT0)") (class "Default")
      (node (ref "IC1") (pin "44") (pinfunction "BOOT0_44") (pintype "input"))
      (node (ref "R1") (pin "1") (pinfunction "1_1") (pintype "passive"))
      (node (ref "S1") (pin "1") (pinfunction "1_1") (pintype "passive"))
      (node (ref "S1") (pin "2") (pinfunction "2_2") (pintype "passive"))
    )
    (net (code "49") (name "Net-(IC1I-NRST)") (class "Default")
      (node (ref "IC1") (pin "7") (pinfunction "NRST_7") (pintype "input"))
      (node (ref "R8") (pin "1") (pinfunction "1_1") (pintype "passive"))
      (node (ref "S2") (pin "1") (pinfunction "1_1") (pintype "passive"))
      (node (ref "S2") (pin "2") (pinfunction "2_2") (pintype "passive"))
    )
    (net (code "50") (name "Net-(LED2-PadC)") (class "Default")
      (node (ref "LED2") (pin "C") (pinfunction "C_C") (pintype "passive"))
      (node (ref "R9") (pin "1") (pinfunction "1_1") (pintype "passive"))
    )
    (net (code "51") (name "Net-(PWR-PadC)") (class "Default")
      (node (ref "PWR") (pin "C") (pinfunction "C_C") (pintype "passive"))
      (node (ref "R7") (pin "2") (pinfunction "2_2") (pintype "passive"))
    )
    (net (code "52") (name "Net-(R4-Pad1)") (class "Default")
      (node (ref "R4") (pin "1") (pinfunction "1_1") (pintype "passive"))
      (node (ref "U$7") (pin "14_VCC_RF") (pinfunction "14_VCC_RF_14_VCC_RF") (pintype "bidirectional"))
    )
    (net (code "53") (name "Net-(TP1-PadTP)") (class "Default")
      (node (ref "TP1") (pin "TP") (pinfunction "TP_TP") (pintype "input"))
      (node (ref "U$7") (pin "5_EXTINT") (pinfunction "5_EXTINT_5_EXTINT") (pintype "bidirectional"))
    )
    (net (code "54") (name "Net-(U$14-PAD)") (class "Default")
      (node (ref "R11") (pin "2") (pinfunction "2_2") (pintype "passive"))
      (node (ref "U$14") (pin "P$1") (pinfunction "PAD_P$1") (pintype "bidirectional"))
    )
    (net (code "55") (name "Net-(U$15-PAD)") (class "Default")
      (node (ref "R10") (pin "2") (pinfunction "2_2") (pintype "passive"))
      (node (ref "U$15") (pin "P$1") (pinfunction "PAD_P$1") (pintype "bidirectional"))
    )
    (net (code "56") (name "Net-(U$16-PAD)") (class "Default")
      (node (ref "R6") (pin "2") (pinfunction "2_2") (pintype "passive"))
      (node (ref "U$16") (pin "P$1") (pinfunction "PAD_P$1") (pintype "bidirectional"))
    )
    (net (code "57") (name "Net-(X1-ANT)") (class "Default")
      (node (ref "L1") (pin "1") (pinfunction "1_1") (pintype "passive"))
      (node (ref "U$7") (pin "11_RF_IN") (pinfunction "11_RF_IN_11_RF_IN") (pintype "bidirectional"))
      (node (ref "X1") (pin "ANTENNA") (pinfunction "ANT_ANTENNA") (pintype "bidirectional"))
    )
    (net (code "58") (name "VBAT") (class "Default")
      (node (ref "G1") (pin "+") (pinfunction "+_+") (pintype "passive"))
      (node (ref "IC1") (pin "1") (pinfunction "VBAT_1") (pintype "power_in"))
      (node (ref "U$7") (pin "6_V_BCKP") (pinfunction "6_V_BCKP_6_V_BCKP") (pintype "bidirectional"))
    )
    (net (code "59") (name "unconnected-(U$1-PadCLK)") (class "Default")
      (node (ref "U$1") (pin "CLK") (pinfunction "CLK_CLK") (pintype "bidirectional"))
    )
    (net (code "60") (name "unconnected-(U$1-PadDIO)") (class "Default")
      (node (ref "U$1") (pin "DIO") (pinfunction "DIO_DIO") (pintype "bidirectional"))
    )
    (net (code "61") (name "unconnected-(U$2-PadCLK)") (class "Default")
      (node (ref "U$2") (pin "CLK") (pinfunction "CLK_CLK") (pintype "bidirectional"))
    )
    (net (code "62") (name "unconnected-(U$2-PadDIO)") (class "Default")
      (node (ref "U$2") (pin "DIO") (pinfunction "DIO_DIO") (pintype "bidirectional"))
    )
    (net (code "63") (name "unconnected-(U$3-PadCLK)") (class "Default")
      (node (ref "U$3") (pin "CLK") (pinfunction "CLK_CLK") (pintype "bidirectional"))
    )
    (net (code "64") (name "unconnected-(U$3-PadDIO)") (class "Default")
      (node (ref "U$3") (pin "DIO") (pinfunction "DIO_DIO") (pintype "bidirectional"))
    )
    (net (code "65") (name "unconnected-(U$4-PadCLK)") (class "Default")
      (node (ref "U$4") (pin "CLK") (pinfunction "CLK_CLK") (pintype "bidirectional"))
    )
    (net (code "66") (name "unconnected-(U$4-PadDIO)") (class "Default")
      (node (ref "U$4") (pin "DIO") (pinfunction "DIO_DIO") (pintype "bidirectional"))
    )
    (net (code "67") (name "unconnected-(U$5-PadCLK)") (class "Default")
      (node (ref "U$5") (pin "CLK") (pinfunction "CLK_CLK") (pintype "bidirectional"))
    )
    (net (code "68") (name "unconnected-(U$5-PadDIO)") (class "Default")
      (node (ref "U$5") (pin "DIO") (pinfunction "DIO_DIO") (pintype "bidirectional"))
    )
    (net (code "69") (name "unconnected-(U$6-PadCLK)") (class "Default")
      (node (ref "U$6") (pin "CLK") (pinfunction "CLK_CLK") (pintype "bidirectional"))
    )
    (net (code "70") (name "unconnected-(U$6-PadDIO)") (class "Default")
      (node (ref "U$6") (pin "DIO") (pinfunction "DIO_DIO") (pintype "bidirectional"))
    )
    (net (code "71") (name "unconnected-(U$7-13_LNA_EN{slash}RES-Pad13_LNA_EN)") (class "Default")
      (node (ref "U$7") (pin "13_LNA_EN") (pinfunction "13_LNA_EN/RES_13_LNA_EN") (pintype "bidirectional"))
    )
    (net (code "72") (name "unconnected-(U$7-15_RES{slash}V_ANT-Pad15_V_ANT{slash}RESERVED)") (class "Default")
      (node (ref "U$7") (pin "15_V_ANT/RESERVED") (pinfunction "15_RES/V_ANT_15_V_ANT/RESERVED") (pintype "bidirectional"))
    )
    (net (code "73") (name "unconnected-(U$7-Pad16_SDA)") (class "Default")
      (node (ref "U$7") (pin "16_SDA") (pinfunction "16_SDA_16_SDA") (pintype "bidirectional"))
    )
    (net (code "74") (name "unconnected-(U$7-Pad17_SCL)") (class "Default")
      (node (ref "U$7") (pin "17_SCL") (pinfunction "17_SCL_17_SCL") (pintype "bidirectional"))
    )
    (net (code "75") (name "unconnected-(U$7-Pad18_SAFEBOOT_N)") (class "Default")
      (node (ref "U$7") (pin "18_SAFEBOOT_N") (pinfunction "18_SAFEBOOT_N_18_SAFEBOOT_N") (pintype "bidirectional"))
    )
  )
)
